# opd_tester.net
KiCad netlist of a schematic drawn in EAGLE
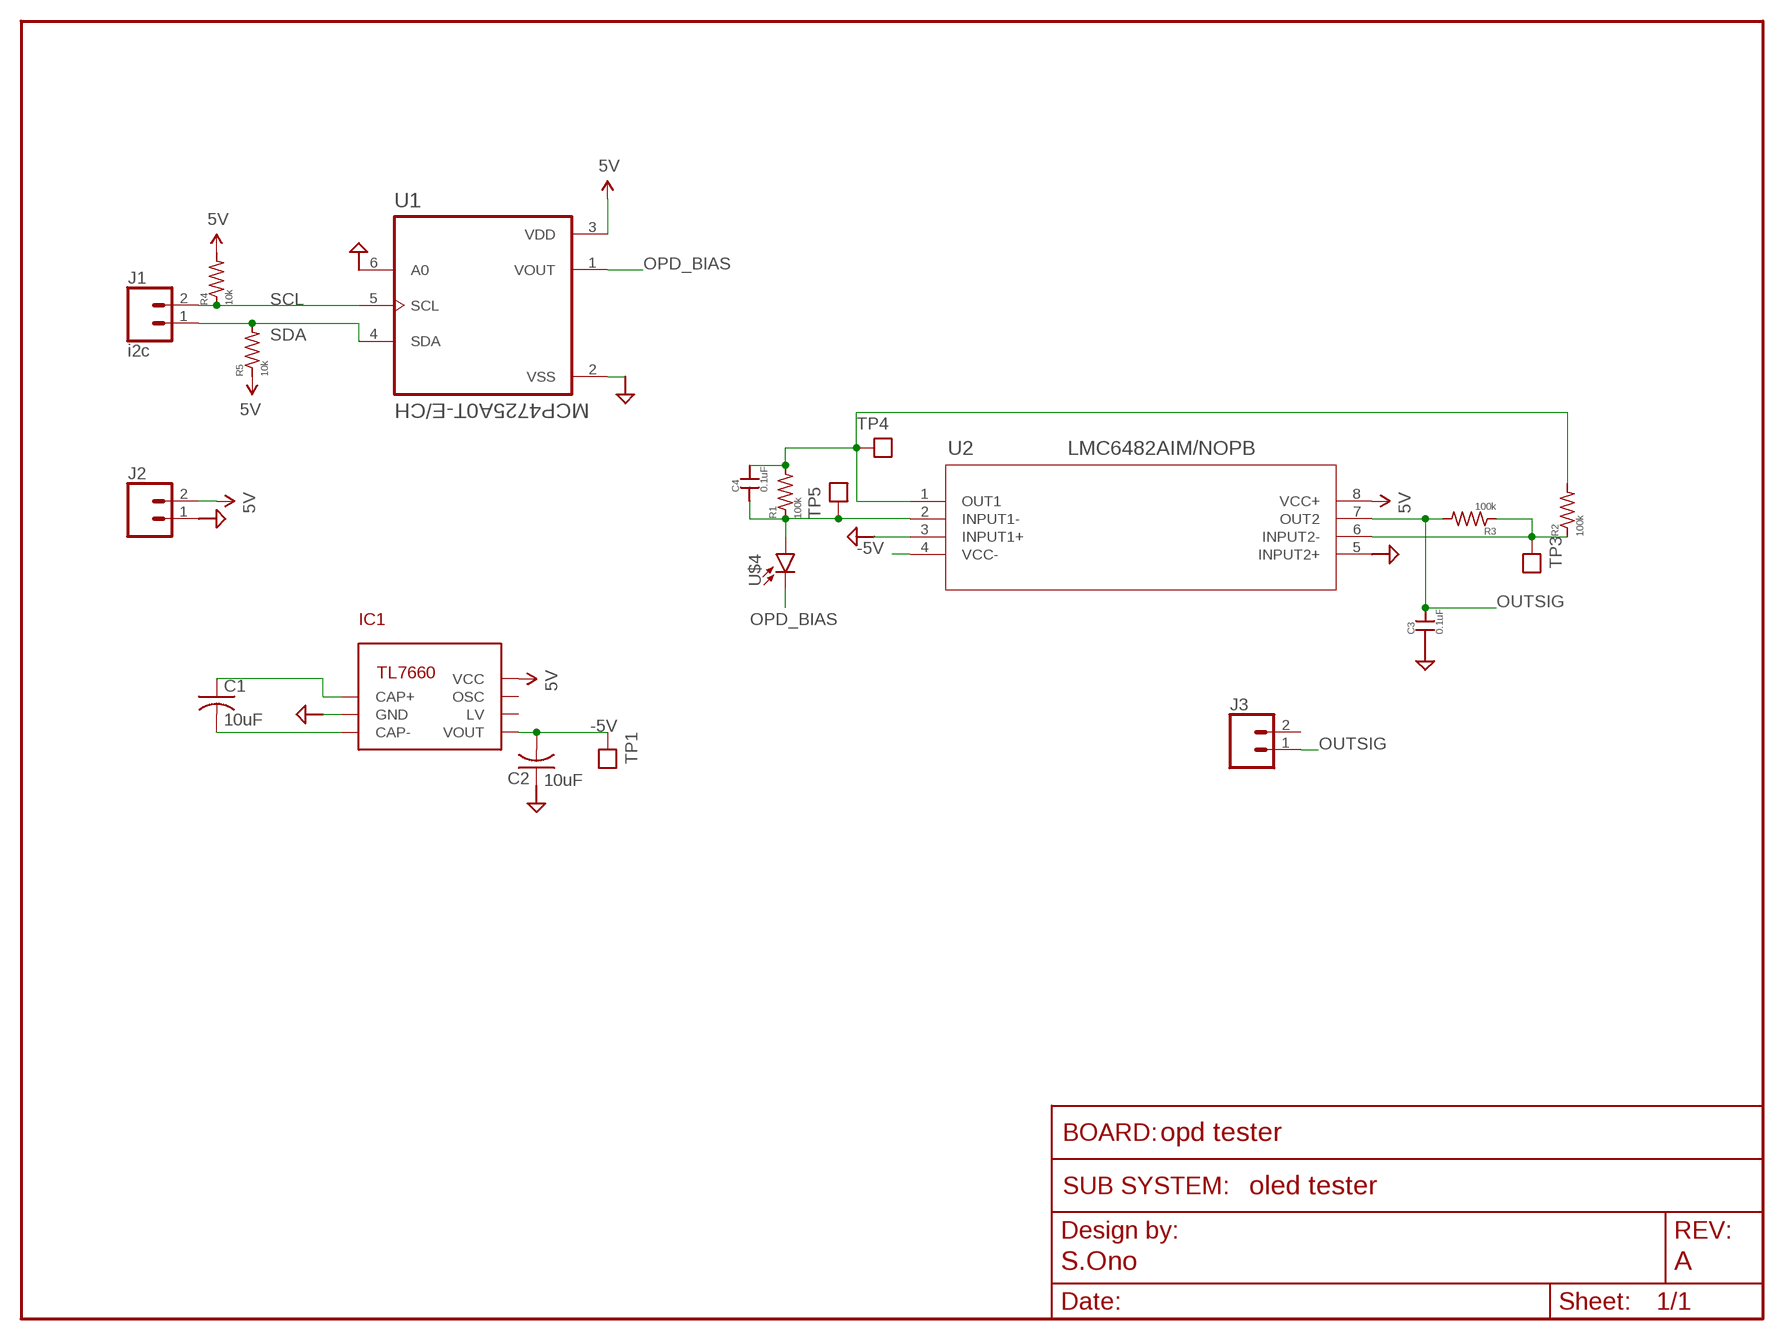
[diagram p0: schematic, sheet 1]

(export (version "E")
  (design (tool "Eeschema 10.0.6"))
  (components
    (comp (ref "C1")
      (value "10uF")
      (footprint "eagle-import:CAP_3MM")
      (libsource (lib "eagle-import") (part "CAP_ELEC_3MM_SMD"))
    )
    (comp (ref "C2")
      (value "10uF")
      (footprint "eagle-import:CAP_3MM")
      (libsource (lib "eagle-import") (part "CAP_ELEC_3MM_SMD"))
    )
    (comp (ref "C3")
      (value "0.1uF")
      (footprint "eagle-import:0603-CAP")
      (libsource (lib "eagle-import") (part "CAP0603-CAP"))
    )
    (comp (ref "C4")
      (value "0.1uF")
      (footprint "eagle-import:0603-CAP")
      (libsource (lib "eagle-import") (part "CAP0603-CAP"))
    )
    (comp (ref "IC1")
      (value "TL7660")
      (footprint "eagle-import:8SOICW")
      (libsource (lib "eagle-import") (part "TL7660"))
    )
    (comp (ref "J1")
      (value "i2c")
      (footprint "eagle-import:1X02")
      (libsource (lib "eagle-import") (part "CONN_02"))
    )
    (comp (ref "J2")
      (value "CONN_02")
      (footprint "eagle-import:1X02")
      (libsource (lib "eagle-import") (part "CONN_02"))
    )
    (comp (ref "J3")
      (value "CONN_02")
      (footprint "eagle-import:1X02")
      (libsource (lib "eagle-import") (part "CONN_02"))
    )
    (comp (ref "R1")
      (value "100k")
      (footprint "eagle-import:0603-RES")
      (libsource (lib "eagle-import") (part "R-US_0603"))
    )
    (comp (ref "R2")
      (value "100k")
      (footprint "eagle-import:0603-RES")
      (libsource (lib "eagle-import") (part "R-US_0603"))
    )
    (comp (ref "R3")
      (value "100k")
      (footprint "eagle-import:0603-RES")
      (libsource (lib "eagle-import") (part "R-US_0603"))
    )
    (comp (ref "R4")
      (value "10k")
      (footprint "eagle-import:0603-RES")
      (libsource (lib "eagle-import") (part "R-US_0603"))
    )
    (comp (ref "R5")
      (value "10k")
      (footprint "eagle-import:0603-RES")
      (libsource (lib "eagle-import") (part "R-US_0603"))
    )
    (comp (ref "TP1")
      (value "TEST_POINTTHRU")
      (footprint "eagle-import:TEST_POINT")
      (libsource (lib "eagle-import") (part "TEST_POINTTHRU"))
    )
    (comp (ref "TP3")
      (value "TEST_POINTTHRU")
      (footprint "eagle-import:TEST_POINT")
      (libsource (lib "eagle-import") (part "TEST_POINTTHRU"))
    )
    (comp (ref "TP4")
      (value "TEST_POINTTHRU")
      (footprint "eagle-import:TEST_POINT")
      (libsource (lib "eagle-import") (part "TEST_POINTTHRU"))
    )
    (comp (ref "TP5")
      (value "TEST_POINTTHRU")
      (footprint "eagle-import:TEST_POINT")
      (libsource (lib "eagle-import") (part "TEST_POINTTHRU"))
    )
    (comp (ref "U$4")
      (value "XDCR_SFH_229")
      (footprint "eagle-import:XDCR_SFH_229")
      (libsource (lib "eagle-import") (part "XDCR_SFH_229"))
    )
    (comp (ref "U1")
      (value "MCP4725A0T-E/CH")
      (footprint "eagle-import:SOT95P270X145-6N")
      (fields (field (name "DIGI-KEY_PART_NUMBER") "MCP4725A0T-E/CHCT-ND") (field (name "MF") "Microchip"))
      (libsource (lib "eagle-import") (part "MCP4725A0T-E/CH"))
    )
    (comp (ref "U2")
      (value "LMC6482AIM/NOPB")
      (footprint "eagle-import:M08A")
      (libsource (lib "eagle-import") (part "LMC6482AIM/NOPB"))
    )
  )
  (nets
    (net (code "1") (name "/-5V") (class "Default")
      (node (ref "C2") (pin "NEG") (pinfunction "NEG_NEG") (pintype "passive"))
      (node (ref "IC1") (pin "5") (pinfunction "VOUT_5") (pintype "bidirectional"))
      (node (ref "TP1") (pin "1") (pinfunction "P$1_1") (pintype "bidirectional"))
      (node (ref "U2") (pin "4") (pinfunction "VCC-_4") (pintype "passive"))
    )
    (net (code "2") (name "/OPD_BIAS") (class "Default")
      (node (ref "U$4") (pin "2") (pinfunction "C_2") (pintype "passive"))
      (node (ref "U1") (pin "1") (pinfunction "VOUT_1") (pintype "output"))
    )
    (net (code "3") (name "/OUTSIG") (class "Default")
      (node (ref "C3") (pin "2") (pinfunction "2_2") (pintype "passive"))
      (node (ref "J3") (pin "1") (pinfunction "1_1") (pintype "passive"))
      (node (ref "R3") (pin "2") (pinfunction "2_2") (pintype "passive"))
      (node (ref "U2") (pin "7") (pinfunction "OUT2_7") (pintype "passive"))
    )
    (net (code "4") (name "/SCL") (class "Default")
      (node (ref "J1") (pin "2") (pinfunction "2_2") (pintype "passive"))
      (node (ref "R4") (pin "1") (pinfunction "1_1") (pintype "passive"))
      (node (ref "U1") (pin "5") (pinfunction "SCL_5") (pintype "input"))
    )
    (net (code "5") (name "/SDA") (class "Default")
      (node (ref "J1") (pin "1") (pinfunction "1_1") (pintype "passive"))
      (node (ref "R5") (pin "2") (pinfunction "2_2") (pintype "passive"))
      (node (ref "U1") (pin "4") (pinfunction "SDA_4") (pintype "bidirectional"))
    )
    (net (code "6") (name "5V") (class "Default")
      (node (ref "IC1") (pin "8") (pinfunction "VCC_8") (pintype "bidirectional"))
      (node (ref "J2") (pin "2") (pinfunction "2_2") (pintype "passive"))
      (node (ref "R4") (pin "2") (pinfunction "2_2") (pintype "passive"))
      (node (ref "R5") (pin "1") (pinfunction "1_1") (pintype "passive"))
      (node (ref "U1") (pin "3") (pinfunction "VDD_3") (pintype "power_in"))
      (node (ref "U2") (pin "8") (pinfunction "VCC+_8") (pintype "passive"))
    )
    (net (code "7") (name "GND") (class "Default")
      (node (ref "C2") (pin "POS") (pinfunction "POS_POS") (pintype "passive"))
      (node (ref "C3") (pin "1") (pinfunction "1_1") (pintype "passive"))
      (node (ref "IC1") (pin "3") (pinfunction "GND_3") (pintype "bidirectional"))
      (node (ref "J2") (pin "1") (pinfunction "1_1") (pintype "passive"))
      (node (ref "U1") (pin "2") (pinfunction "VSS_2") (pintype "power_in"))
      (node (ref "U1") (pin "6") (pinfunction "A0_6") (pintype "input"))
      (node (ref "U2") (pin "3") (pinfunction "INPUT1+_3") (pintype "passive"))
      (node (ref "U2") (pin "5") (pinfunction "INPUT2+_5") (pintype "passive"))
    )
    (net (code "8") (name "Net-(IC1-CAP+)") (class "Default")
      (node (ref "C1") (pin "POS") (pinfunction "POS_POS") (pintype "passive"))
      (node (ref "IC1") (pin "2") (pinfunction "CAP+_2") (pintype "bidirectional"))
    )
    (net (code "9") (name "Net-(IC1-CAP-)") (class "Default")
      (node (ref "C1") (pin "NEG") (pinfunction "NEG_NEG") (pintype "passive"))
      (node (ref "IC1") (pin "4") (pinfunction "CAP-_4") (pintype "bidirectional"))
    )
    (net (code "10") (name "Net-(TP3-P$1)") (class "Default")
      (node (ref "R2") (pin "1") (pinfunction "1_1") (pintype "passive"))
      (node (ref "R3") (pin "1") (pinfunction "1_1") (pintype "passive"))
      (node (ref "TP3") (pin "1") (pinfunction "P$1_1") (pintype "bidirectional"))
      (node (ref "U2") (pin "6") (pinfunction "INPUT2-_6") (pintype "passive"))
    )
    (net (code "11") (name "Net-(TP4-P$1)") (class "Default")
      (node (ref "C4") (pin "2") (pinfunction "2_2") (pintype "passive"))
      (node (ref "R1") (pin "2") (pinfunction "2_2") (pintype "passive"))
      (node (ref "R2") (pin "2") (pinfunction "2_2") (pintype "passive"))
      (node (ref "TP4") (pin "1") (pinfunction "P$1_1") (pintype "bidirectional"))
      (node (ref "U2") (pin "1") (pinfunction "OUT1_1") (pintype "passive"))
    )
    (net (code "12") (name "Net-(TP5-P$1)") (class "Default")
      (node (ref "C4") (pin "1") (pinfunction "1_1") (pintype "passive"))
      (node (ref "R1") (pin "1") (pinfunction "1_1") (pintype "passive"))
      (node (ref "TP5") (pin "1") (pinfunction "P$1_1") (pintype "bidirectional"))
      (node (ref "U$4") (pin "1") (pinfunction "A_1") (pintype "passive"))
      (node (ref "U2") (pin "2") (pinfunction "INPUT1-_2") (pintype "passive"))
    )
    (net (code "13") (name "unconnected-(IC1-LV-Pad6)") (class "Default")
      (node (ref "IC1") (pin "6") (pinfunction "LV_6") (pintype "bidirectional"))
    )
    (net (code "14") (name "unconnected-(IC1-OSC-Pad7)") (class "Default")
      (node (ref "IC1") (pin "7") (pinfunction "OSC_7") (pintype "bidirectional"))
    )
    (net (code "15") (name "unconnected-(J3-Pad2)") (class "Default")
      (node (ref "J3") (pin "2") (pinfunction "2_2") (pintype "passive"))
    )
  )
)
